# Lagopus_A_3.net
KiCad netlist of a schematic drawn in EAGLE
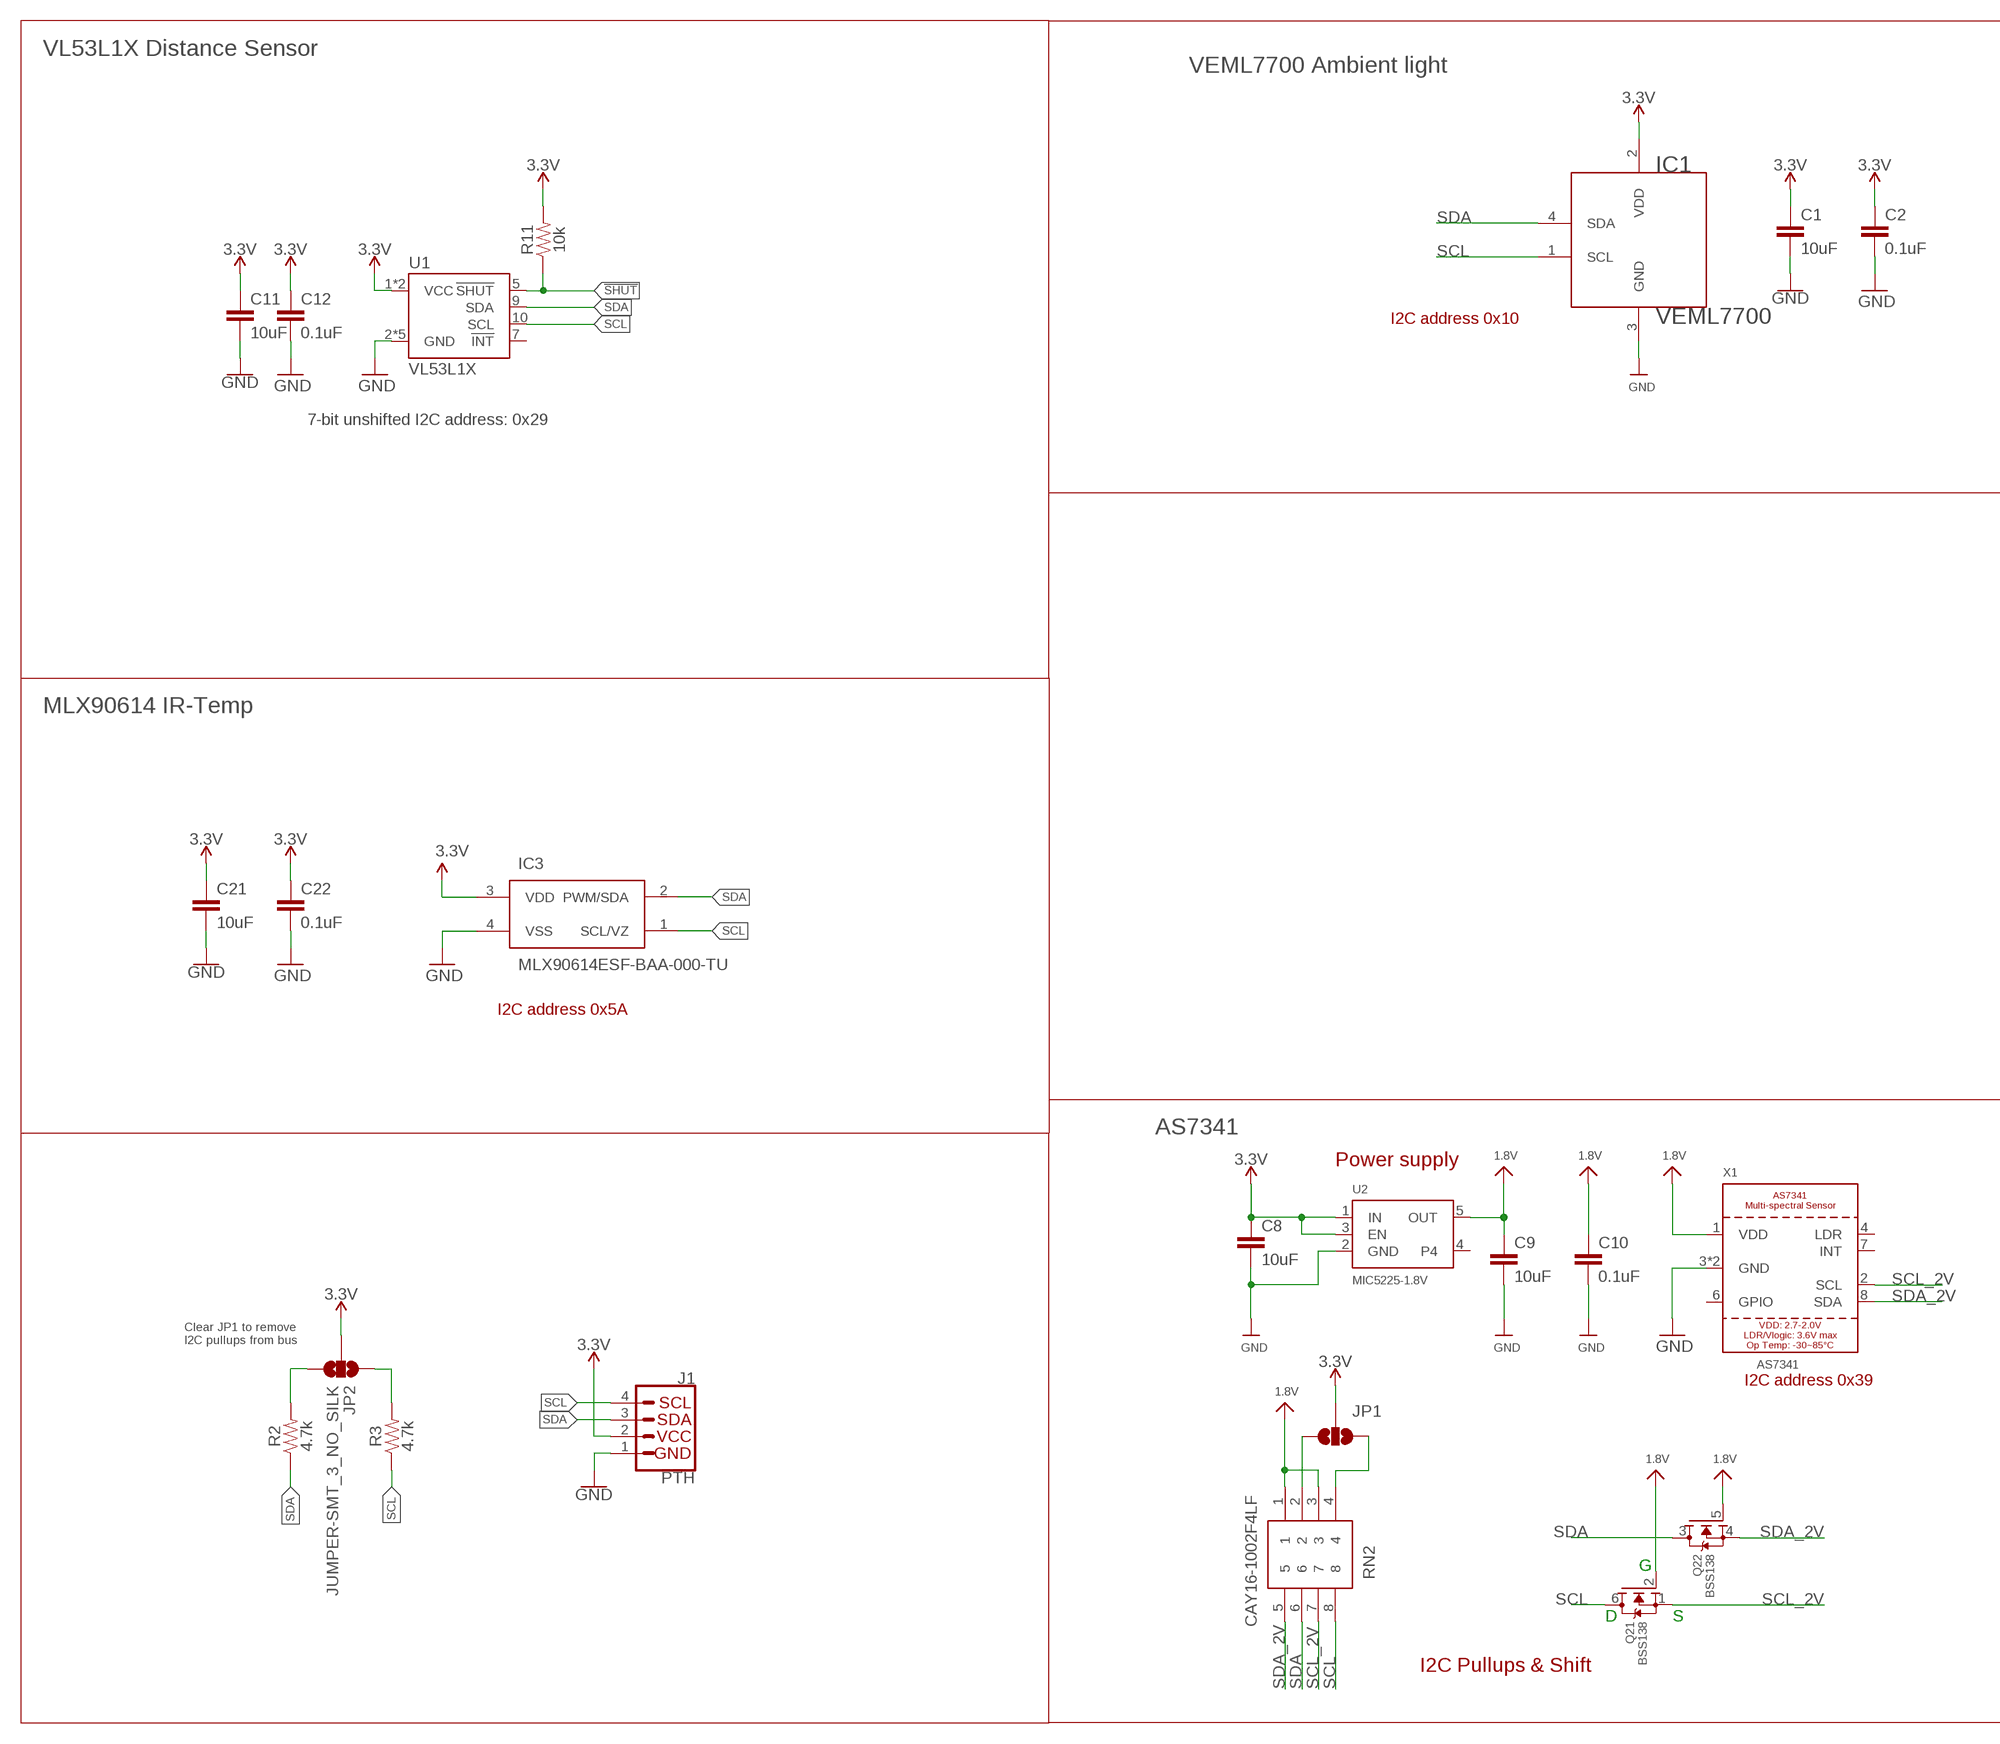
[diagram p0: schematic, sheet 1, part 1 of 2]
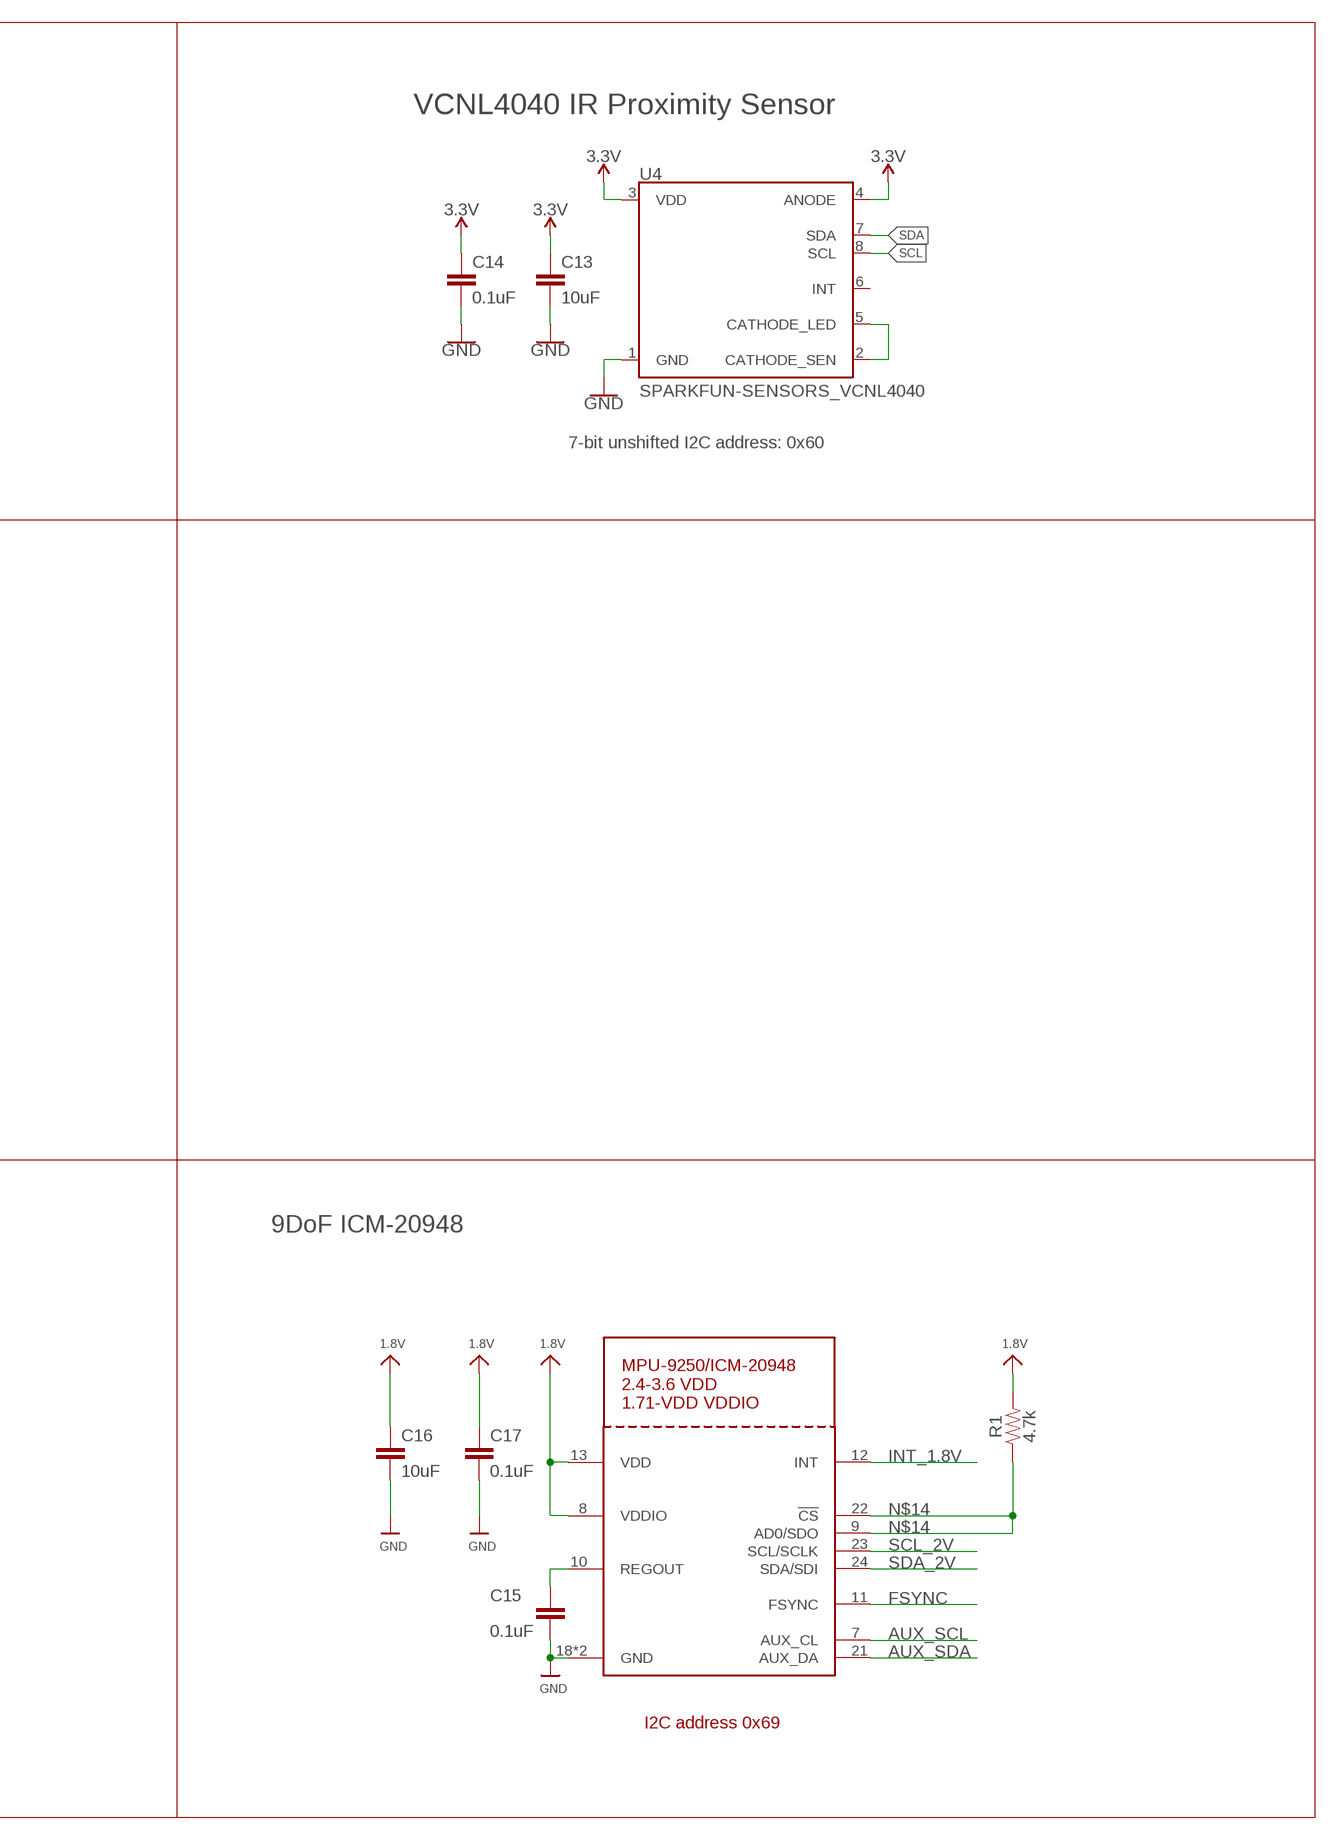
[diagram p1: schematic, sheet 1, part 2 of 2]

(export (version "E")
  (design (tool "Eeschema 10.0.6"))
  (components
    (comp (ref "C1")
      (value "10uF")
      (footprint "eagle-import:0603")
      (libsource (lib "eagle-import") (part "10UF-0603-6.3V-20%"))
    )
    (comp (ref "C2")
      (value "0.1uF")
      (footprint "eagle-import:0603")
      (libsource (lib "eagle-import") (part "SparkFun-Capacitors_510_0.1UF-0603-25V-(+80/-20%)"))
    )
    (comp (ref "C8")
      (value "10uF")
      (footprint "eagle-import:0603")
      (libsource (lib "eagle-import") (part "10UF-0603-6.3V-20%"))
    )
    (comp (ref "C9")
      (value "10uF")
      (footprint "eagle-import:0603")
      (libsource (lib "eagle-import") (part "10UF-0603-6.3V-20%"))
    )
    (comp (ref "C10")
      (value "0.1uF")
      (footprint "eagle-import:0603")
      (libsource (lib "eagle-import") (part "SparkFun-Capacitors_510_0.1UF-0603-25V-(+80/-20%)"))
    )
    (comp (ref "C11")
      (value "10uF")
      (footprint "eagle-import:0603")
      (libsource (lib "eagle-import") (part "10UF-0603-6.3V-20%"))
    )
    (comp (ref "C12")
      (value "0.1uF")
      (footprint "eagle-import:0603")
      (libsource (lib "eagle-import") (part "SparkFun-Capacitors_510_0.1UF-0603-25V-(+80/-20%)"))
    )
    (comp (ref "C13")
      (value "10uF")
      (footprint "eagle-import:0603")
      (libsource (lib "eagle-import") (part "10UF-0603-6.3V-20%"))
    )
    (comp (ref "C14")
      (value "0.1uF")
      (footprint "eagle-import:0603")
      (libsource (lib "eagle-import") (part "0.1UF-0603-25V-(+80/-20%)"))
    )
    (comp (ref "C15")
      (value "0.1uF")
      (footprint "eagle-import:0603")
      (libsource (lib "eagle-import") (part "SparkFun-Capacitors_510_0.1UF-0603-25V-(+80/-20%)"))
    )
    (comp (ref "C16")
      (value "10uF")
      (footprint "eagle-import:0603")
      (libsource (lib "eagle-import") (part "10UF-0603-6.3V-20%"))
    )
    (comp (ref "C17")
      (value "0.1uF")
      (footprint "eagle-import:0603")
      (libsource (lib "eagle-import") (part "SparkFun-Capacitors_510_0.1UF-0603-25V-(+80/-20%)"))
    )
    (comp (ref "C21")
      (value "10uF")
      (footprint "eagle-import:0603")
      (libsource (lib "eagle-import") (part "10UF-0603-6.3V-20%"))
    )
    (comp (ref "C22")
      (value "0.1uF")
      (footprint "eagle-import:0603")
      (libsource (lib "eagle-import") (part "SparkFun-Capacitors_510_0.1UF-0603-25V-(+80/-20%)"))
    )
    (comp (ref "IC1")
      (value "VEML7700")
      (footprint "eagle-import:VEML7700")
      (libsource (lib "eagle-import") (part "VEML7700"))
    )
    (comp (ref "IC3")
      (value "MLX90614ESF-BAA-000-TU")
      (footprint "eagle-import:MLX90614ESFBAA000TU")
      (fields (field (name "RS_PART_NUMBER") "1942939"))
      (libsource (lib "eagle-import") (part "MLX90614ESF-BAA-000-TU"))
    )
    (comp (ref "J1")
      (value "PTH")
      (footprint "eagle-import:1X04_NO_SILK")
      (libsource (lib "eagle-import") (part "I2C_STANDARD_NO_SILK"))
    )
    (comp (ref "JP1")
      (value "JUMPER-SMT_3_NO_SILK")
      (footprint "eagle-import:SMT-JUMPER_3_NO_SILK")
      (libsource (lib "eagle-import") (part "JUMPER-SMT_3_NO_SILK"))
    )
    (comp (ref "JP2")
      (value "JUMPER-SMT_3_NO_SILK")
      (footprint "eagle-import:SMT-JUMPER_3_NO_SILK")
      (libsource (lib "eagle-import") (part "JUMPER-SMT_3_NO_SILK"))
    )
    (comp (ref "Q2")
      (value "BSS138")
      (footprint "eagle-import:SOT363")
      (libsource (lib "eagle-import") (part "MOSFET-N_DUAL"))
    )
    (comp (ref "R1")
      (value "4.7k")
      (footprint "eagle-import:0603")
      (libsource (lib "eagle-import") (part "4.7KOHM-0603-1/10W-1%"))
    )
    (comp (ref "R2")
      (value "4.7k")
      (footprint "eagle-import:0603")
      (libsource (lib "eagle-import") (part "4.7KOHM-0603-1/10W-1%"))
    )
    (comp (ref "R3")
      (value "4.7k")
      (footprint "eagle-import:0603")
      (libsource (lib "eagle-import") (part "4.7KOHM-0603-1/10W-1%"))
    )
    (comp (ref "R11")
      (value "10k")
      (footprint "eagle-import:0603")
      (libsource (lib "eagle-import") (part "10KOHM-0603-1/10W-1%"))
    )
    (comp (ref "RN2")
      (value "CAY16-1002F4LF")
      (footprint "eagle-import:CAY-16-F4")
      (fields (field (name "RS_PART_NUMBER") "7408767P"))
      (libsource (lib "eagle-import") (part "CAY16-1002F4LF"))
    )
    (comp (ref "U$21")
      (value "MPU-9250_ICM20948")
      (footprint "eagle-import:QFN24_3MM_NOEP")
      (libsource (lib "eagle-import") (part "MPU-9250_ICM20948"))
    )
    (comp (ref "U1")
      (value "VL53L1X")
      (footprint "eagle-import:VL53L1X")
      (libsource (lib "eagle-import") (part "VL53L1XSMD"))
    )
    (comp (ref "U2")
      (value "MIC5225-1.8V")
      (footprint "eagle-import:SOT23-5")
      (libsource (lib "eagle-import") (part "VREG_SOT23-5"))
    )
    (comp (ref "U4")
      (value "SPARKFUN-SENSORS_VCNL4040")
      (footprint "eagle-import:SPARKFUN-SENSORS_SPARKX_VCNL4040")
      (libsource (lib "eagle-import") (part "SPARKFUN-SENSORS_VCNL4040"))
    )
    (comp (ref "X1")
      (value "AS7341")
      (footprint "eagle-import:AS7341")
      (libsource (lib "eagle-import") (part "AS7341"))
    )
  )
  (nets
    (net (code "1") (name "/AUX_SCL") (class "Default")
      (node (ref "U$21") (pin "7") (pinfunction "AUX_CL_7") (pintype "bidirectional"))
    )
    (net (code "2") (name "/AUX_SDA") (class "Default")
      (node (ref "U$21") (pin "21") (pinfunction "AUX_DA_21") (pintype "bidirectional"))
    )
    (net (code "3") (name "/FSYNC") (class "Default")
      (node (ref "U$21") (pin "11") (pinfunction "FSYNC_11") (pintype "bidirectional"))
    )
    (net (code "4") (name "/GPIO") (class "Default")
      (node (ref "X1") (pin "6") (pinfunction "GPIO_6") (pintype "power_in"))
    )
    (net (code "5") (name "/INT_1.8V") (class "Default")
      (node (ref "U$21") (pin "12") (pinfunction "INT_12") (pintype "bidirectional"))
    )
    (net (code "6") (name "/N$14") (class "Default")
      (node (ref "R1") (pin "1") (pinfunction "1_1") (pintype "passive"))
      (node (ref "U$21") (pin "22") (pinfunction "~{CS}_22") (pintype "bidirectional"))
      (node (ref "U$21") (pin "9") (pinfunction "AD0/SDO_9") (pintype "bidirectional"))
    )
    (net (code "7") (name "/SCL_2V") (class "Default")
      (node (ref "Q2") (pin "1") (pinfunction "S_1") (pintype "bidirectional"))
      (node (ref "RN2") (pin "7") (pinfunction "7_7") (pintype "bidirectional"))
      (node (ref "U$21") (pin "23") (pinfunction "SCL/SCLK_23") (pintype "bidirectional"))
      (node (ref "X1") (pin "2") (pinfunction "SCL_2") (pintype "input"))
    )
    (net (code "8") (name "/SDA_2V") (class "Default")
      (node (ref "Q2") (pin "4") (pinfunction "S_4") (pintype "bidirectional"))
      (node (ref "RN2") (pin "5") (pinfunction "5_5") (pintype "bidirectional"))
      (node (ref "U$21") (pin "24") (pinfunction "SDA/SDI_24") (pintype "bidirectional"))
      (node (ref "X1") (pin "8") (pinfunction "SDA_8") (pintype "bidirectional"))
    )
    (net (code "9") (name "/~{SHUT}") (class "Default")
      (node (ref "R11") (pin "1") (pinfunction "1_1") (pintype "passive"))
      (node (ref "U1") (pin "5") (pinfunction "~{SHUT}_5") (pintype "bidirectional"))
    )
    (net (code "10") (name "1.8V") (class "Default")
      (node (ref "C10") (pin "1") (pinfunction "1_1") (pintype "passive"))
      (node (ref "C16") (pin "1") (pinfunction "1_1") (pintype "passive"))
      (node (ref "C17") (pin "1") (pinfunction "1_1") (pintype "passive"))
      (node (ref "C9") (pin "1") (pinfunction "1_1") (pintype "passive"))
      (node (ref "Q2") (pin "2") (pinfunction "G_2") (pintype "bidirectional"))
      (node (ref "Q2") (pin "5") (pinfunction "G_5") (pintype "bidirectional"))
      (node (ref "R1") (pin "2") (pinfunction "2_2") (pintype "passive"))
      (node (ref "RN2") (pin "1") (pinfunction "1_1") (pintype "bidirectional"))
      (node (ref "RN2") (pin "3") (pinfunction "3_3") (pintype "bidirectional"))
      (node (ref "U$21") (pin "13") (pinfunction "VDD_13") (pintype "bidirectional"))
      (node (ref "U$21") (pin "8") (pinfunction "VDDIO_8") (pintype "bidirectional"))
      (node (ref "U2") (pin "5") (pinfunction "OUT_5") (pintype "power_in"))
      (node (ref "X1") (pin "1") (pinfunction "VDD_1") (pintype "power_in"))
    )
    (net (code "11") (name "3.3V") (class "Default")
      (node (ref "C1") (pin "1") (pinfunction "1_1") (pintype "passive"))
      (node (ref "C11") (pin "1") (pinfunction "1_1") (pintype "passive"))
      (node (ref "C12") (pin "1") (pinfunction "1_1") (pintype "passive"))
      (node (ref "C13") (pin "1") (pinfunction "1_1") (pintype "passive"))
      (node (ref "C14") (pin "1") (pinfunction "1_1") (pintype "passive"))
      (node (ref "C2") (pin "1") (pinfunction "1_1") (pintype "passive"))
      (node (ref "C21") (pin "1") (pinfunction "1_1") (pintype "passive"))
      (node (ref "C22") (pin "1") (pinfunction "1_1") (pintype "passive"))
      (node (ref "C8") (pin "1") (pinfunction "1_1") (pintype "passive"))
      (node (ref "IC1") (pin "2") (pinfunction "VDD_2") (pintype "power_in"))
      (node (ref "IC3") (pin "3") (pinfunction "VDD_3") (pintype "bidirectional"))
      (node (ref "J1") (pin "2") (pinfunction "VCC_2") (pintype "power_in"))
      (node (ref "JP1") (pin "2") (pinfunction "2_2") (pintype "passive"))
      (node (ref "JP2") (pin "2") (pinfunction "2_2") (pintype "passive"))
      (node (ref "R11") (pin "2") (pinfunction "2_2") (pintype "passive"))
      (node (ref "U1") (pin "1") (pinfunction "VCC_1") (pintype "bidirectional"))
      (node (ref "U1") (pin "11") (pinfunction "VCC_11") (pintype "bidirectional"))
      (node (ref "U2") (pin "1") (pinfunction "IN_1") (pintype "power_in"))
      (node (ref "U2") (pin "3") (pinfunction "EN_3") (pintype "input"))
      (node (ref "U4") (pin "3") (pinfunction "VDD_3") (pintype "bidirectional"))
      (node (ref "U4") (pin "4") (pinfunction "ANODE_4") (pintype "bidirectional"))
    )
    (net (code "12") (name "GND") (class "Default")
      (node (ref "C1") (pin "2") (pinfunction "2_2") (pintype "passive"))
      (node (ref "C10") (pin "2") (pinfunction "2_2") (pintype "passive"))
      (node (ref "C11") (pin "2") (pinfunction "2_2") (pintype "passive"))
      (node (ref "C12") (pin "2") (pinfunction "2_2") (pintype "passive"))
      (node (ref "C13") (pin "2") (pinfunction "2_2") (pintype "passive"))
      (node (ref "C14") (pin "2") (pinfunction "2_2") (pintype "passive"))
      (node (ref "C15") (pin "2") (pinfunction "2_2") (pintype "passive"))
      (node (ref "C16") (pin "2") (pinfunction "2_2") (pintype "passive"))
      (node (ref "C17") (pin "2") (pinfunction "2_2") (pintype "passive"))
      (node (ref "C2") (pin "2") (pinfunction "2_2") (pintype "passive"))
      (node (ref "C21") (pin "2") (pinfunction "2_2") (pintype "passive"))
      (node (ref "C22") (pin "2") (pinfunction "2_2") (pintype "passive"))
      (node (ref "C8") (pin "2") (pinfunction "2_2") (pintype "passive"))
      (node (ref "C9") (pin "2") (pinfunction "2_2") (pintype "passive"))
      (node (ref "IC1") (pin "3") (pinfunction "GND_3") (pintype "power_in"))
      (node (ref "IC3") (pin "4") (pinfunction "VSS_4") (pintype "power_in"))
      (node (ref "J1") (pin "1") (pinfunction "GND_1") (pintype "power_in"))
      (node (ref "U$21") (pin "18") (pinfunction "GND_18") (pintype "bidirectional"))
      (node (ref "U$21") (pin "20") (pinfunction "GND_20") (pintype "bidirectional"))
      (node (ref "U1") (pin "12") (pinfunction "GND_12") (pintype "bidirectional"))
      (node (ref "U1") (pin "2") (pinfunction "GND_2") (pintype "bidirectional"))
      (node (ref "U1") (pin "3") (pinfunction "GND_3") (pintype "bidirectional"))
      (node (ref "U1") (pin "4") (pinfunction "GND_4") (pintype "bidirectional"))
      (node (ref "U1") (pin "6") (pinfunction "GND_6") (pintype "bidirectional"))
      (node (ref "U2") (pin "2") (pinfunction "GND_2") (pintype "power_in"))
      (node (ref "U4") (pin "1") (pinfunction "GND_1") (pintype "bidirectional"))
      (node (ref "X1") (pin "3") (pinfunction "GND_3") (pintype "power_in"))
      (node (ref "X1") (pin "5") (pinfunction "GND_5") (pintype "power_in"))
    )
    (net (code "13") (name "Net-(JP1-Pad1)") (class "Default")
      (node (ref "JP1") (pin "1") (pinfunction "1_1") (pintype "passive"))
      (node (ref "RN2") (pin "2") (pinfunction "2_2") (pintype "bidirectional"))
    )
    (net (code "14") (name "Net-(JP1-Pad3)") (class "Default")
      (node (ref "JP1") (pin "3") (pinfunction "3_3") (pintype "passive"))
      (node (ref "RN2") (pin "4") (pinfunction "4_4") (pintype "bidirectional"))
    )
    (net (code "15") (name "Net-(JP2-Pad1)") (class "Default")
      (node (ref "JP2") (pin "1") (pinfunction "1_1") (pintype "passive"))
      (node (ref "R3") (pin "2") (pinfunction "2_2") (pintype "passive"))
    )
    (net (code "16") (name "Net-(JP2-Pad3)") (class "Default")
      (node (ref "JP2") (pin "3") (pinfunction "3_3") (pintype "passive"))
      (node (ref "R2") (pin "2") (pinfunction "2_2") (pintype "passive"))
    )
    (net (code "17") (name "Net-(U$21-REGOUT)") (class "Default")
      (node (ref "C15") (pin "1") (pinfunction "1_1") (pintype "passive"))
      (node (ref "U$21") (pin "10") (pinfunction "REGOUT_10") (pintype "bidirectional"))
    )
    (net (code "18") (name "Net-(U4-CATHODE_LED)") (class "Default")
      (node (ref "U4") (pin "2") (pinfunction "CATHODE_SEN_2") (pintype "bidirectional"))
      (node (ref "U4") (pin "5") (pinfunction "CATHODE_LED_5") (pintype "bidirectional"))
    )
    (net (code "19") (name "SCL") (class "Default")
      (node (ref "IC1") (pin "1") (pinfunction "SCL_1") (pintype "bidirectional"))
      (node (ref "IC3") (pin "1") (pinfunction "SCL/VZ_1") (pintype "bidirectional"))
      (node (ref "J1") (pin "4") (pinfunction "SCL_4") (pintype "passive"))
      (node (ref "Q2") (pin "6") (pinfunction "D_6") (pintype "bidirectional"))
      (node (ref "R3") (pin "1") (pinfunction "1_1") (pintype "passive"))
      (node (ref "RN2") (pin "8") (pinfunction "8_8") (pintype "bidirectional"))
      (node (ref "U1") (pin "10") (pinfunction "SCL_10") (pintype "bidirectional"))
      (node (ref "U4") (pin "8") (pinfunction "SCL_8") (pintype "bidirectional"))
    )
    (net (code "20") (name "SDA") (class "Default")
      (node (ref "IC1") (pin "4") (pinfunction "SDA_4") (pintype "bidirectional"))
      (node (ref "IC3") (pin "2") (pinfunction "PWM/SDA_2") (pintype "power_in"))
      (node (ref "J1") (pin "3") (pinfunction "SDA_3") (pintype "passive"))
      (node (ref "Q2") (pin "3") (pinfunction "D_3") (pintype "bidirectional"))
      (node (ref "R2") (pin "1") (pinfunction "1_1") (pintype "passive"))
      (node (ref "RN2") (pin "6") (pinfunction "6_6") (pintype "bidirectional"))
      (node (ref "U1") (pin "9") (pinfunction "SDA_9") (pintype "bidirectional"))
      (node (ref "U4") (pin "7") (pinfunction "SDA_7") (pintype "bidirectional"))
    )
    (net (code "21") (name "unconnected-(U1-~{INT}-Pad7)") (class "Default")
      (node (ref "U1") (pin "7") (pinfunction "~{INT}_7") (pintype "bidirectional"))
    )
    (net (code "22") (name "unconnected-(U2-P4-Pad4)") (class "Default")
      (node (ref "U2") (pin "4") (pinfunction "P4_4") (pintype "bidirectional"))
    )
    (net (code "23") (name "unconnected-(U4-INT-Pad6)") (class "Default")
      (node (ref "U4") (pin "6") (pinfunction "INT_6") (pintype "bidirectional"))
    )
    (net (code "24") (name "unconnected-(X1-INT-Pad7)") (class "Default")
      (node (ref "X1") (pin "7") (pinfunction "INT_7") (pintype "output"))
    )
    (net (code "25") (name "unconnected-(X1-LDR-Pad4)") (class "Default")
      (node (ref "X1") (pin "4") (pinfunction "LDR_4") (pintype "bidirectional"))
    )
  )
)
